# Flame.net
KiCad netlist of a schematic drawn in Altium Designer
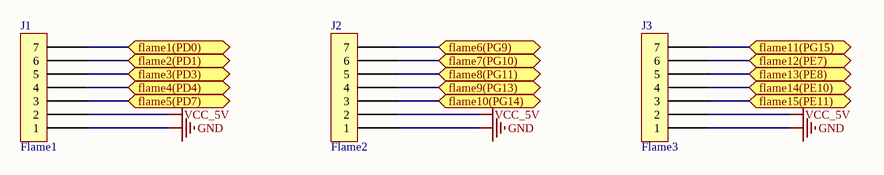
[diagram p0: Flame.SchDoc]

(export (version "E")
  (design (tool "Eeschema 10.0.6"))
  (components
    (comp (ref "J1")
      (value "Flame1")
      (footprint "XH2.54-LI-7P")
      (libsource (lib "ZH1.5") (part "Component_1"))
    )
    (comp (ref "J2")
      (value "Flame2")
      (footprint "XH2.54-LI-7P")
      (libsource (lib "ZH1.5") (part "Component_1"))
    )
    (comp (ref "J3")
      (value "Flame3")
      (footprint "XH2.54-LI-7P")
      (libsource (lib "ZH1.5") (part "Component_1"))
    )
  )
  (nets
    (net (code "1") (name "/flame1(PD0)") (class "Default")
      (node (ref "J1") (pin "7") (pinfunction "7_7") (pintype "passive"))
    )
    (net (code "2") (name "/flame2(PD1)") (class "Default")
      (node (ref "J1") (pin "6") (pinfunction "6_6") (pintype "passive"))
    )
    (net (code "3") (name "/flame3(PD3)") (class "Default")
      (node (ref "J1") (pin "5") (pinfunction "5_5") (pintype "passive"))
    )
    (net (code "4") (name "/flame4(PD4)") (class "Default")
      (node (ref "J1") (pin "4") (pinfunction "4_4") (pintype "passive"))
    )
    (net (code "5") (name "/flame5(PD7)") (class "Default")
      (node (ref "J1") (pin "3") (pinfunction "3_3") (pintype "passive"))
    )
    (net (code "6") (name "/flame6(PG9)") (class "Default")
      (node (ref "J2") (pin "7") (pinfunction "7_7") (pintype "passive"))
    )
    (net (code "7") (name "/flame7(PG10)") (class "Default")
      (node (ref "J2") (pin "6") (pinfunction "6_6") (pintype "passive"))
    )
    (net (code "8") (name "/flame8(PG11)") (class "Default")
      (node (ref "J2") (pin "5") (pinfunction "5_5") (pintype "passive"))
    )
    (net (code "9") (name "/flame9(PG13)") (class "Default")
      (node (ref "J2") (pin "4") (pinfunction "4_4") (pintype "passive"))
    )
    (net (code "10") (name "/flame10(PG14)") (class "Default")
      (node (ref "J2") (pin "3") (pinfunction "3_3") (pintype "passive"))
    )
    (net (code "11") (name "/flame11(PG15)") (class "Default")
      (node (ref "J3") (pin "7") (pinfunction "7_7") (pintype "passive"))
    )
    (net (code "12") (name "/flame12(PE7)") (class "Default")
      (node (ref "J3") (pin "6") (pinfunction "6_6") (pintype "passive"))
    )
    (net (code "13") (name "/flame13(PE8)") (class "Default")
      (node (ref "J3") (pin "5") (pinfunction "5_5") (pintype "passive"))
    )
    (net (code "14") (name "/flame14(PE10)") (class "Default")
      (node (ref "J3") (pin "4") (pinfunction "4_4") (pintype "passive"))
    )
    (net (code "15") (name "/flame15(PE11)") (class "Default")
      (node (ref "J3") (pin "3") (pinfunction "3_3") (pintype "passive"))
    )
    (net (code "16") (name "GND") (class "Default")
      (node (ref "J1") (pin "1") (pinfunction "1_1") (pintype "passive"))
      (node (ref "J2") (pin "1") (pinfunction "1_1") (pintype "passive"))
      (node (ref "J3") (pin "1") (pinfunction "1_1") (pintype "passive"))
    )
    (net (code "17") (name "VCC_5V") (class "Default")
      (node (ref "J1") (pin "2") (pinfunction "2_2") (pintype "passive"))
      (node (ref "J2") (pin "2") (pinfunction "2_2") (pintype "passive"))
      (node (ref "J3") (pin "2") (pinfunction "2_2") (pintype "passive"))
    )
  )
)
